# Display.net
KiCad netlist of a schematic drawn in Altium Designer
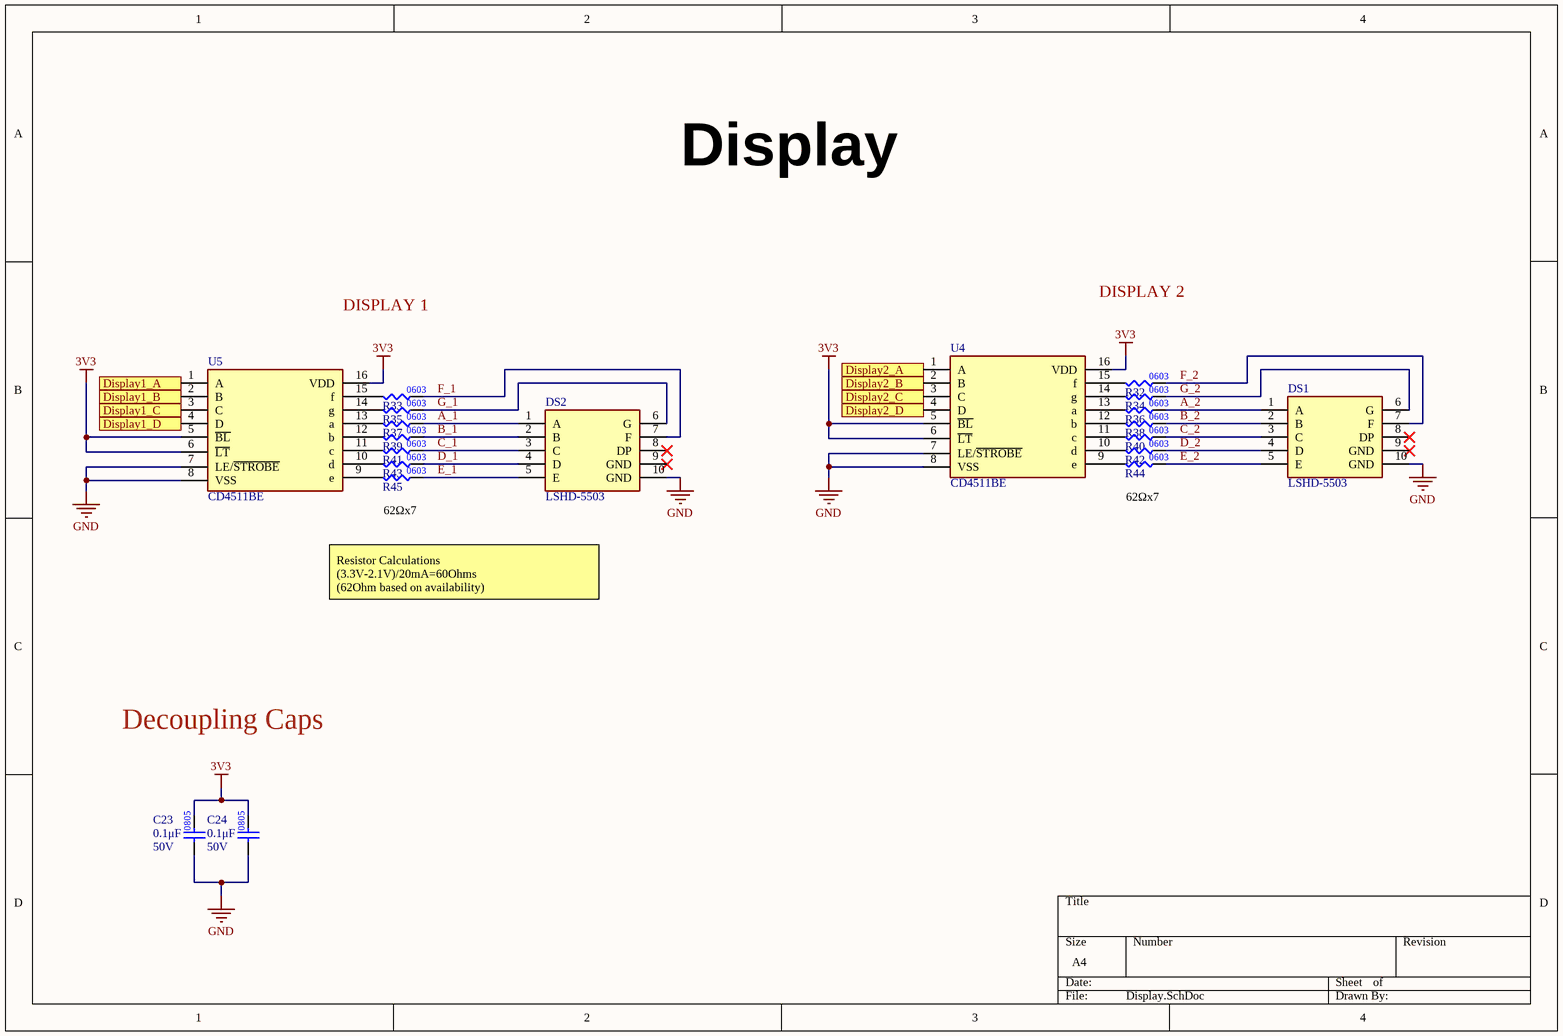
[diagram p0: Display.SchDoc]

(export (version "E")
  (design (tool "Eeschema 10.0.6"))
  (components
    (comp (ref "C23")
      (value "0.1μF")
      (footprint "CAP2012")
      (description "CAP CER 0.1UF 50V X7R 0805")
      (fields
        (field (name "VOLTAGE RATING") "50V")
        (field (name "LCSC PART #") "C49678")
        (field (name "Comment") "CAP_0.1uF_50V_0805")
      )
      (libsource (lib "UWRT_Schematic_Library_2020") (part "CAP_0.1uF_50V_0805"))
    )
    (comp (ref "C24")
      (value "0.1μF")
      (footprint "CAP2012")
      (description "CAP CER 0.1UF 50V X7R 0805")
      (fields
        (field (name "VOLTAGE RATING") "50V")
        (field (name "LCSC PART #") "C49678")
        (field (name "Comment") "CAP_0.1uF_50V_0805")
      )
      (libsource (lib "UWRT_Schematic_Library_2020") (part "CAP_0.1uF_50V_0805"))
    )
    (comp (ref "DS1")
      (value "LSHD-5503")
      (footprint "DIPS1524W50P254L1240H825Q10N")
      (description "DISPLAY 7SEG 0.56\" SGL RED 10DIP")
      (fields (field (name "MOUSER PART NUMBER") "859-LSHD-5503"))
      (libsource (lib "UWRT_Schematic_Library_2020") (part "LSHD-5503"))
    )
    (comp (ref "DS2")
      (value "LSHD-5503")
      (footprint "DIPS1524W50P254L1240H825Q10N")
      (description "DISPLAY 7SEG 0.56\" SGL RED 10DIP")
      (fields (field (name "MOUSER PART NUMBER") "859-LSHD-5503"))
      (libsource (lib "UWRT_Schematic_Library_2020") (part "LSHD-5503"))
    )
    (comp (ref "R32")
      (value "RES_62Ω_0603_1%")
      (description "RES 62 OHM 1% 1/10W 0603")
      (fields (field (name "MANUFACTURER") "Vishay"))
      (libsource (lib "UWRT_Schematic_Library_2020") (part "RES_62Ω_0603_1%"))
    )
    (comp (ref "R33")
      (value "RES_62Ω_0603_1%")
      (description "RES 62 OHM 1% 1/10W 0603")
      (fields (field (name "MANUFACTURER") "Vishay"))
      (libsource (lib "UWRT_Schematic_Library_2020") (part "RES_62Ω_0603_1%"))
    )
    (comp (ref "R34")
      (value "RES_62Ω_0603_1%")
      (description "RES 62 OHM 1% 1/10W 0603")
      (fields (field (name "MANUFACTURER") "Vishay"))
      (libsource (lib "UWRT_Schematic_Library_2020") (part "RES_62Ω_0603_1%"))
    )
    (comp (ref "R35")
      (value "RES_62Ω_0603_1%")
      (description "RES 62 OHM 1% 1/10W 0603")
      (fields (field (name "MANUFACTURER") "Vishay"))
      (libsource (lib "UWRT_Schematic_Library_2020") (part "RES_62Ω_0603_1%"))
    )
    (comp (ref "R36")
      (value "RES_62Ω_0603_1%")
      (description "RES 62 OHM 1% 1/10W 0603")
      (fields (field (name "MANUFACTURER") "Vishay"))
      (libsource (lib "UWRT_Schematic_Library_2020") (part "RES_62Ω_0603_1%"))
    )
    (comp (ref "R37")
      (value "RES_62Ω_0603_1%")
      (description "RES 62 OHM 1% 1/10W 0603")
      (fields (field (name "MANUFACTURER") "Vishay"))
      (libsource (lib "UWRT_Schematic_Library_2020") (part "RES_62Ω_0603_1%"))
    )
    (comp (ref "R38")
      (value "RES_62Ω_0603_1%")
      (description "RES 62 OHM 1% 1/10W 0603")
      (fields (field (name "MANUFACTURER") "Vishay"))
      (libsource (lib "UWRT_Schematic_Library_2020") (part "RES_62Ω_0603_1%"))
    )
    (comp (ref "R39")
      (value "RES_62Ω_0603_1%")
      (description "RES 62 OHM 1% 1/10W 0603")
      (fields (field (name "MANUFACTURER") "Vishay"))
      (libsource (lib "UWRT_Schematic_Library_2020") (part "RES_62Ω_0603_1%"))
    )
    (comp (ref "R40")
      (value "RES_62Ω_0603_1%")
      (description "RES 62 OHM 1% 1/10W 0603")
      (fields (field (name "MANUFACTURER") "Vishay"))
      (libsource (lib "UWRT_Schematic_Library_2020") (part "RES_62Ω_0603_1%"))
    )
    (comp (ref "R41")
      (value "RES_62Ω_0603_1%")
      (description "RES 62 OHM 1% 1/10W 0603")
      (fields (field (name "MANUFACTURER") "Vishay"))
      (libsource (lib "UWRT_Schematic_Library_2020") (part "RES_62Ω_0603_1%"))
    )
    (comp (ref "R42")
      (value "RES_62Ω_0603_1%")
      (description "RES 62 OHM 1% 1/10W 0603")
      (fields (field (name "MANUFACTURER") "Vishay"))
      (libsource (lib "UWRT_Schematic_Library_2020") (part "RES_62Ω_0603_1%"))
    )
    (comp (ref "R43")
      (value "RES_62Ω_0603_1%")
      (description "RES 62 OHM 1% 1/10W 0603")
      (fields (field (name "MANUFACTURER") "Vishay"))
      (libsource (lib "UWRT_Schematic_Library_2020") (part "RES_62Ω_0603_1%"))
    )
    (comp (ref "R44")
      (value "RES_62Ω_0603_1%")
      (description "RES 62 OHM 1% 1/10W 0603")
      (fields (field (name "MANUFACTURER") "Vishay"))
      (libsource (lib "UWRT_Schematic_Library_2020") (part "RES_62Ω_0603_1%"))
    )
    (comp (ref "R45")
      (value "RES_62Ω_0603_1%")
      (description "RES 62 OHM 1% 1/10W 0603")
      (fields (field (name "MANUFACTURER") "Vishay"))
      (libsource (lib "UWRT_Schematic_Library_2020") (part "RES_62Ω_0603_1%"))
    )
    (comp (ref "U4")
      (value "CD4511BE")
      (footprint "DIP794W53P254L1930H508Q16N")
      (description "Integrated Circuit")
      (fields (field (name "MOUSER PART NUMBER") "595-CD4511BE"))
      (libsource (lib "UWRT_Schematic_Library_2020") (part "CD4511BE"))
    )
    (comp (ref "U5")
      (value "CD4511BE")
      (footprint "DIP794W53P254L1930H508Q16N")
      (description "Integrated Circuit")
      (fields (field (name "MOUSER PART NUMBER") "595-CD4511BE"))
      (libsource (lib "UWRT_Schematic_Library_2020") (part "CD4511BE"))
    )
  )
  (nets
    (net (code "1") (name "/A_1") (class "Default")
      (node (ref "DS2") (pin "1") (pinfunction "A_1") (pintype "passive"))
      (node (ref "R37") (pin "2") (pinfunction "2_2") (pintype "passive"))
    )
    (net (code "2") (name "/A_2") (class "Default")
      (node (ref "DS1") (pin "1") (pinfunction "A_1") (pintype "passive"))
      (node (ref "R36") (pin "2") (pinfunction "2_2") (pintype "passive"))
    )
    (net (code "3") (name "/B_1") (class "Default")
      (node (ref "DS2") (pin "2") (pinfunction "B_2") (pintype "passive"))
      (node (ref "R39") (pin "2") (pinfunction "2_2") (pintype "passive"))
    )
    (net (code "4") (name "/B_2") (class "Default")
      (node (ref "DS1") (pin "2") (pinfunction "B_2") (pintype "passive"))
      (node (ref "R38") (pin "2") (pinfunction "2_2") (pintype "passive"))
    )
    (net (code "5") (name "/C_1") (class "Default")
      (node (ref "DS2") (pin "3") (pinfunction "C_3") (pintype "passive"))
      (node (ref "R41") (pin "2") (pinfunction "2_2") (pintype "passive"))
    )
    (net (code "6") (name "/C_2") (class "Default")
      (node (ref "DS1") (pin "3") (pinfunction "C_3") (pintype "passive"))
      (node (ref "R40") (pin "2") (pinfunction "2_2") (pintype "passive"))
    )
    (net (code "7") (name "/D_1") (class "Default")
      (node (ref "DS2") (pin "4") (pinfunction "D_4") (pintype "passive"))
      (node (ref "R43") (pin "2") (pinfunction "2_2") (pintype "passive"))
    )
    (net (code "8") (name "/D_2") (class "Default")
      (node (ref "DS1") (pin "4") (pinfunction "D_4") (pintype "passive"))
      (node (ref "R42") (pin "2") (pinfunction "2_2") (pintype "passive"))
    )
    (net (code "9") (name "/Display1_A") (class "Default")
      (node (ref "U5") (pin "1") (pinfunction "A_1") (pintype "passive"))
    )
    (net (code "10") (name "/Display1_B") (class "Default")
      (node (ref "U5") (pin "2") (pinfunction "B_2") (pintype "passive"))
    )
    (net (code "11") (name "/Display1_C") (class "Default")
      (node (ref "U5") (pin "3") (pinfunction "C_3") (pintype "passive"))
    )
    (net (code "12") (name "/Display1_D") (class "Default")
      (node (ref "U5") (pin "4") (pinfunction "D_4") (pintype "passive"))
    )
    (net (code "13") (name "/Display2_A") (class "Default")
      (node (ref "U4") (pin "1") (pinfunction "A_1") (pintype "passive"))
    )
    (net (code "14") (name "/Display2_B") (class "Default")
      (node (ref "U4") (pin "2") (pinfunction "B_2") (pintype "passive"))
    )
    (net (code "15") (name "/Display2_C") (class "Default")
      (node (ref "U4") (pin "3") (pinfunction "C_3") (pintype "passive"))
    )
    (net (code "16") (name "/Display2_D") (class "Default")
      (node (ref "U4") (pin "4") (pinfunction "D_4") (pintype "passive"))
    )
    (net (code "17") (name "/E_1") (class "Default")
      (node (ref "DS2") (pin "5") (pinfunction "E_5") (pintype "passive"))
      (node (ref "R45") (pin "2") (pinfunction "2_2") (pintype "passive"))
    )
    (net (code "18") (name "/E_2") (class "Default")
      (node (ref "DS1") (pin "5") (pinfunction "E_5") (pintype "passive"))
      (node (ref "R44") (pin "2") (pinfunction "2_2") (pintype "passive"))
    )
    (net (code "19") (name "/F_1") (class "Default")
      (node (ref "DS2") (pin "7") (pinfunction "F_7") (pintype "passive"))
      (node (ref "R33") (pin "2") (pinfunction "2_2") (pintype "passive"))
    )
    (net (code "20") (name "/F_2") (class "Default")
      (node (ref "DS1") (pin "7") (pinfunction "F_7") (pintype "passive"))
      (node (ref "R32") (pin "2") (pinfunction "2_2") (pintype "passive"))
    )
    (net (code "21") (name "/G_1") (class "Default")
      (node (ref "DS2") (pin "6") (pinfunction "G_6") (pintype "passive"))
      (node (ref "R35") (pin "2") (pinfunction "2_2") (pintype "passive"))
    )
    (net (code "22") (name "/G_2") (class "Default")
      (node (ref "DS1") (pin "6") (pinfunction "G_6") (pintype "passive"))
      (node (ref "R34") (pin "2") (pinfunction "2_2") (pintype "passive"))
    )
    (net (code "23") (name "3V3") (class "Default")
      (node (ref "C23") (pin "2") (pinfunction "2_2") (pintype "passive"))
      (node (ref "C24") (pin "2") (pinfunction "2_2") (pintype "passive"))
      (node (ref "U4") (pin "16") (pinfunction "VDD_16") (pintype "passive"))
      (node (ref "U4") (pin "5") (pinfunction "~{BL}_5") (pintype "passive"))
      (node (ref "U4") (pin "6") (pinfunction "~{LT}_6") (pintype "passive"))
      (node (ref "U5") (pin "16") (pinfunction "VDD_16") (pintype "passive"))
      (node (ref "U5") (pin "5") (pinfunction "~{BL}_5") (pintype "passive"))
      (node (ref "U5") (pin "6") (pinfunction "~{LT}_6") (pintype "passive"))
    )
    (net (code "24") (name "GND") (class "Default")
      (node (ref "C23") (pin "1") (pinfunction "1_1") (pintype "passive"))
      (node (ref "C24") (pin "1") (pinfunction "1_1") (pintype "passive"))
      (node (ref "DS1") (pin "10") (pinfunction "GND_10") (pintype "passive"))
      (node (ref "DS2") (pin "10") (pinfunction "GND_10") (pintype "passive"))
      (node (ref "U4") (pin "7") (pinfunction "LE/~{STROBE}_7") (pintype "passive"))
      (node (ref "U4") (pin "8") (pinfunction "VSS_8") (pintype "passive"))
      (node (ref "U5") (pin "7") (pinfunction "LE/~{STROBE}_7") (pintype "passive"))
      (node (ref "U5") (pin "8") (pinfunction "VSS_8") (pintype "passive"))
    )
    (net (code "25") (name "Net-(U4-a)") (class "Default")
      (node (ref "R36") (pin "1") (pinfunction "1_1") (pintype "passive"))
      (node (ref "U4") (pin "13") (pinfunction "a_13") (pintype "passive"))
    )
    (net (code "26") (name "Net-(U4-b)") (class "Default")
      (node (ref "R38") (pin "1") (pinfunction "1_1") (pintype "passive"))
      (node (ref "U4") (pin "12") (pinfunction "b_12") (pintype "passive"))
    )
    (net (code "27") (name "Net-(U4-c)") (class "Default")
      (node (ref "R40") (pin "1") (pinfunction "1_1") (pintype "passive"))
      (node (ref "U4") (pin "11") (pinfunction "c_11") (pintype "passive"))
    )
    (net (code "28") (name "Net-(U4-d)") (class "Default")
      (node (ref "R42") (pin "1") (pinfunction "1_1") (pintype "passive"))
      (node (ref "U4") (pin "10") (pinfunction "d_10") (pintype "passive"))
    )
    (net (code "29") (name "Net-(U4-e)") (class "Default")
      (node (ref "R44") (pin "1") (pinfunction "1_1") (pintype "passive"))
      (node (ref "U4") (pin "9") (pinfunction "e_9") (pintype "passive"))
    )
    (net (code "30") (name "Net-(U4-f)") (class "Default")
      (node (ref "R32") (pin "1") (pinfunction "1_1") (pintype "passive"))
      (node (ref "U4") (pin "15") (pinfunction "f_15") (pintype "passive"))
    )
    (net (code "31") (name "Net-(U4-g)") (class "Default")
      (node (ref "R34") (pin "1") (pinfunction "1_1") (pintype "passive"))
      (node (ref "U4") (pin "14") (pinfunction "g_14") (pintype "passive"))
    )
    (net (code "32") (name "Net-(U5-a)") (class "Default")
      (node (ref "R37") (pin "1") (pinfunction "1_1") (pintype "passive"))
      (node (ref "U5") (pin "13") (pinfunction "a_13") (pintype "passive"))
    )
    (net (code "33") (name "Net-(U5-b)") (class "Default")
      (node (ref "R39") (pin "1") (pinfunction "1_1") (pintype "passive"))
      (node (ref "U5") (pin "12") (pinfunction "b_12") (pintype "passive"))
    )
    (net (code "34") (name "Net-(U5-c)") (class "Default")
      (node (ref "R41") (pin "1") (pinfunction "1_1") (pintype "passive"))
      (node (ref "U5") (pin "11") (pinfunction "c_11") (pintype "passive"))
    )
    (net (code "35") (name "Net-(U5-d)") (class "Default")
      (node (ref "R43") (pin "1") (pinfunction "1_1") (pintype "passive"))
      (node (ref "U5") (pin "10") (pinfunction "d_10") (pintype "passive"))
    )
    (net (code "36") (name "Net-(U5-e)") (class "Default")
      (node (ref "R45") (pin "1") (pinfunction "1_1") (pintype "passive"))
      (node (ref "U5") (pin "9") (pinfunction "e_9") (pintype "passive"))
    )
    (net (code "37") (name "Net-(U5-f)") (class "Default")
      (node (ref "R33") (pin "1") (pinfunction "1_1") (pintype "passive"))
      (node (ref "U5") (pin "15") (pinfunction "f_15") (pintype "passive"))
    )
    (net (code "38") (name "Net-(U5-g)") (class "Default")
      (node (ref "R35") (pin "1") (pinfunction "1_1") (pintype "passive"))
      (node (ref "U5") (pin "14") (pinfunction "g_14") (pintype "passive"))
    )
    (net (code "39") (name "unconnected-(DS1-DP-Pad8)") (class "Default")
      (node (ref "DS1") (pin "8") (pinfunction "DP_8") (pintype "passive+no_connect"))
    )
    (net (code "40") (name "unconnected-(DS1-GND-Pad9)") (class "Default")
      (node (ref "DS1") (pin "9") (pinfunction "GND_9") (pintype "passive+no_connect"))
    )
    (net (code "41") (name "unconnected-(DS2-DP-Pad8)") (class "Default")
      (node (ref "DS2") (pin "8") (pinfunction "DP_8") (pintype "passive+no_connect"))
    )
    (net (code "42") (name "unconnected-(DS2-GND-Pad9)") (class "Default")
      (node (ref "DS2") (pin "9") (pinfunction "GND_9") (pintype "passive+no_connect"))
    )
  )
)
